# baseband.net
KiCad netlist of a schematic drawn in Altium Designer
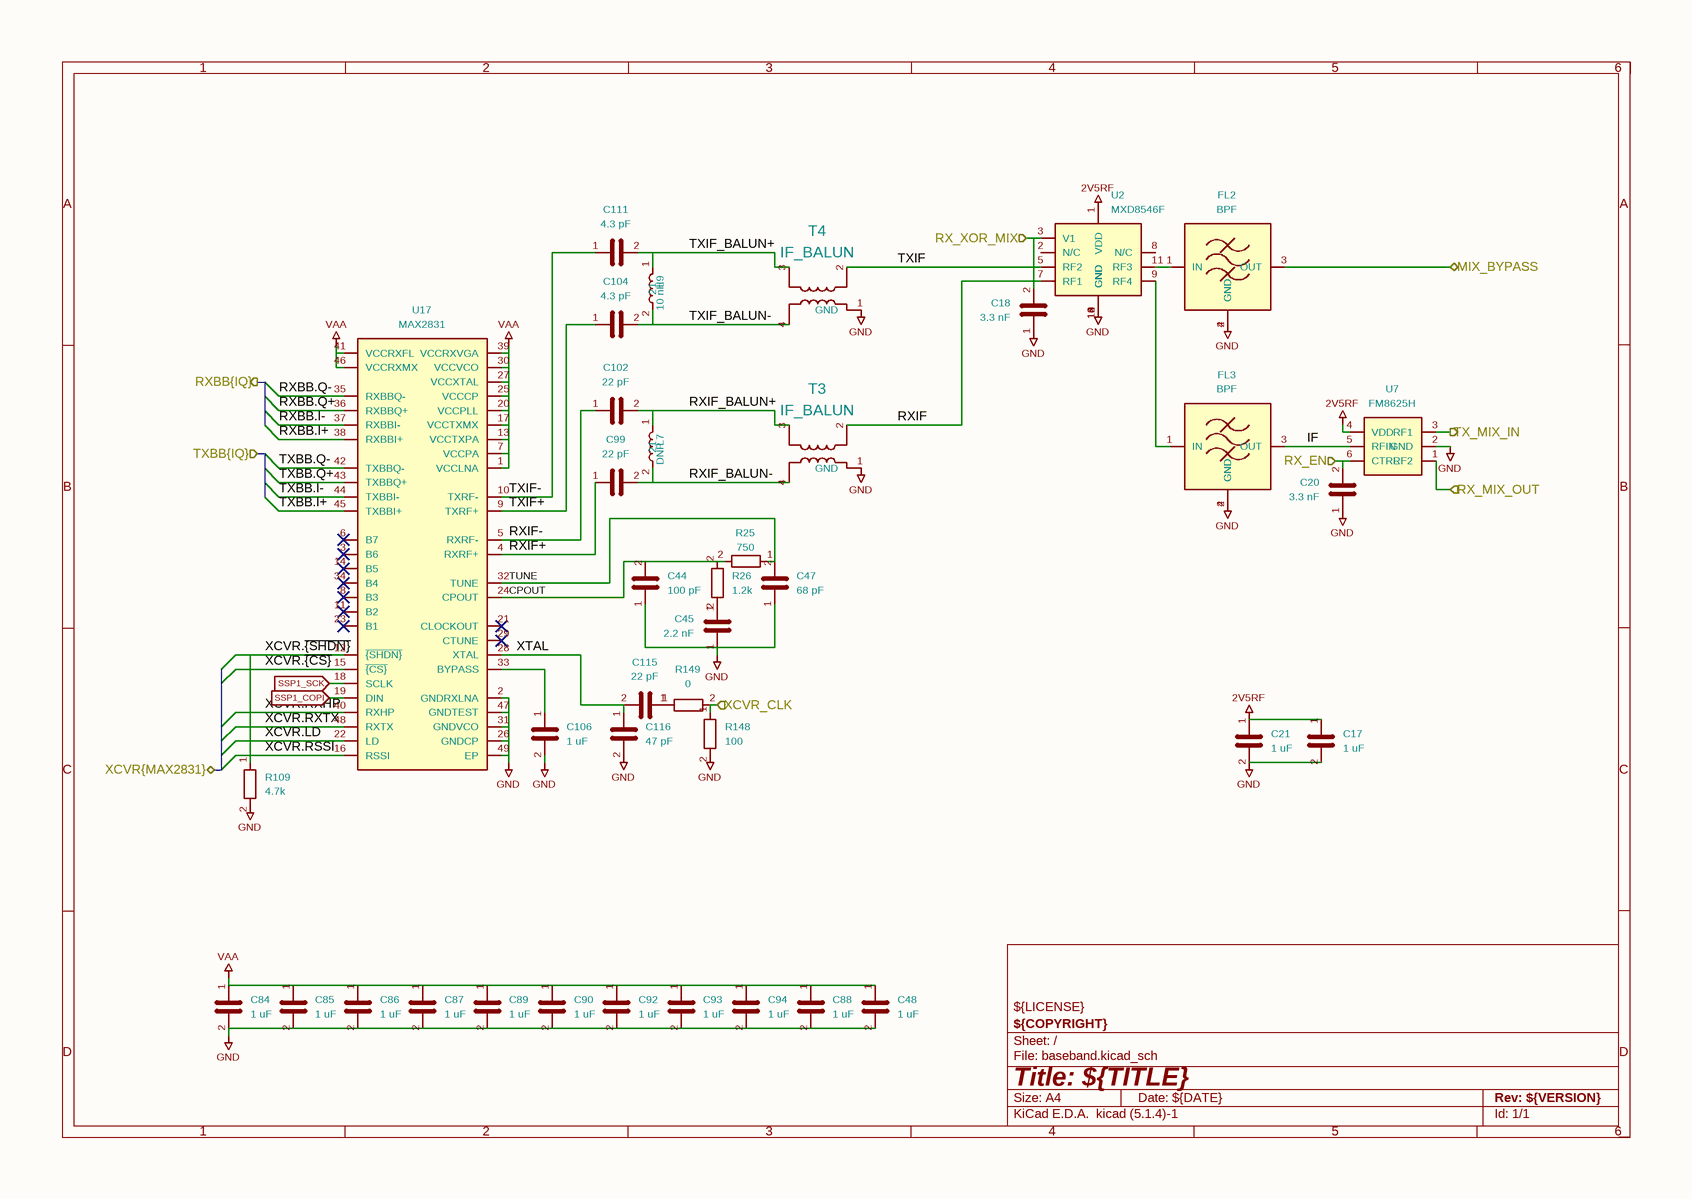
[diagram p0: baseband.SchDoc]

(export (version "E")
  (design (tool "Eeschema 10.0.6"))
  (components
    (comp (ref "C17")
      (value "1 uF")
      (footprint "C_0201_0603Metric")
      (description "CAP CER 1UF 10V X5R 0201")
      (fields (field (name "MANUFACTURER") "Murata") (field (name "PART NUMBER") "GRM033R61A105ME44D"))
      (libsource (lib "Device") (part "C"))
    )
    (comp (ref "C18")
      (value "3.3 nF")
      (footprint "C_0201_0603Metric")
      (description "CAP CER 3300PF 10V X7R 0201")
      (fields (field (name "MANUFACTURER") "Murata") (field (name "PART NUMBER") "GRM033R71A332KA01D"))
      (libsource (lib "Device") (part "C"))
    )
    (comp (ref "C20")
      (value "3.3 nF")
      (footprint "C_0201_0603Metric")
      (description "CAP CER 3300PF 10V X7R 0201")
      (fields (field (name "MANUFACTURER") "Murata") (field (name "PART NUMBER") "GRM033R71A332KA01D"))
      (libsource (lib "Device") (part "C"))
    )
    (comp (ref "C21")
      (value "1 uF")
      (footprint "C_0201_0603Metric")
      (description "CAP CER 1UF 10V X5R 0201")
      (fields (field (name "MANUFACTURER") "Murata") (field (name "PART NUMBER") "GRM033R61A105ME44D"))
      (libsource (lib "Device") (part "C"))
    )
    (comp (ref "C44")
      (value "100 pF")
      (footprint "C_0201_0603Metric")
      (description "CAP CER 100PF 25V C0G/NP0 0201")
      (fields (field (name "MANUFACTURER") "Murata") (field (name "PART NUMBER") "GRM0335C1E101JA01D"))
      (libsource (lib "Device") (part "C"))
    )
    (comp (ref "C45")
      (value "2.2 nF")
      (footprint "C_0201_0603Metric")
      (description "CAP CER 2200PF 10V X7R 0201")
      (fields (field (name "MANUFACTURER") "Murata") (field (name "PART NUMBER") "GRM033R71A222KA01D"))
      (libsource (lib "Device") (part "C"))
    )
    (comp (ref "C47")
      (value "68 pF")
      (footprint "C_0201_0603Metric")
      (description "CAP CER 68PF 50V C0G/NP0 0201")
      (fields (field (name "MANUFACTURER") "Murata") (field (name "PART NUMBER") "GRM0335C1H680JA01D"))
      (libsource (lib "Device") (part "C"))
    )
    (comp (ref "C48")
      (value "1 uF")
      (footprint "C_0201_0603Metric")
      (description "CAP CER 1UF 10V X5R 0201")
      (fields (field (name "MANUFACTURER") "Murata") (field (name "PART NUMBER") "GRM033R61A105ME44D"))
      (libsource (lib "Device") (part "C"))
    )
    (comp (ref "C84")
      (value "1 uF")
      (footprint "C_0201_0603Metric")
      (description "CAP CER 1UF 10V X5R 0201")
      (fields (field (name "MANUFACTURER") "Murata") (field (name "PART NUMBER") "GRM033R61A105ME44D"))
      (libsource (lib "Device") (part "C"))
    )
    (comp (ref "C85")
      (value "1 uF")
      (footprint "C_0201_0603Metric")
      (description "CAP CER 1UF 10V X5R 0201")
      (fields (field (name "MANUFACTURER") "Murata") (field (name "PART NUMBER") "GRM033R61A105ME44D"))
      (libsource (lib "Device") (part "C"))
    )
    (comp (ref "C86")
      (value "1 uF")
      (footprint "C_0201_0603Metric")
      (description "CAP CER 1UF 10V X5R 0201")
      (fields (field (name "MANUFACTURER") "Murata") (field (name "PART NUMBER") "GRM033R61A105ME44D"))
      (libsource (lib "Device") (part "C"))
    )
    (comp (ref "C87")
      (value "1 uF")
      (footprint "C_0201_0603Metric")
      (description "CAP CER 1UF 10V X5R 0201")
      (fields (field (name "MANUFACTURER") "Murata") (field (name "PART NUMBER") "GRM033R61A105ME44D"))
      (libsource (lib "Device") (part "C"))
    )
    (comp (ref "C88")
      (value "1 uF")
      (footprint "C_0201_0603Metric")
      (description "CAP CER 1UF 10V X5R 0201")
      (fields (field (name "MANUFACTURER") "Murata") (field (name "PART NUMBER") "GRM033R61A105ME44D"))
      (libsource (lib "Device") (part "C"))
    )
    (comp (ref "C89")
      (value "1 uF")
      (footprint "C_0201_0603Metric")
      (description "CAP CER 1UF 10V X5R 0201")
      (fields (field (name "MANUFACTURER") "Murata") (field (name "PART NUMBER") "GRM033R61A105ME44D"))
      (libsource (lib "Device") (part "C"))
    )
    (comp (ref "C90")
      (value "1 uF")
      (footprint "C_0201_0603Metric")
      (description "CAP CER 1UF 10V X5R 0201")
      (fields (field (name "MANUFACTURER") "Murata") (field (name "PART NUMBER") "GRM033R61A105ME44D"))
      (libsource (lib "Device") (part "C"))
    )
    (comp (ref "C92")
      (value "1 uF")
      (footprint "C_0201_0603Metric")
      (description "CAP CER 1UF 10V X5R 0201")
      (fields (field (name "MANUFACTURER") "Murata") (field (name "PART NUMBER") "GRM033R61A105ME44D"))
      (libsource (lib "Device") (part "C"))
    )
    (comp (ref "C93")
      (value "1 uF")
      (footprint "C_0201_0603Metric")
      (description "CAP CER 1UF 10V X5R 0201")
      (fields (field (name "MANUFACTURER") "Murata") (field (name "PART NUMBER") "GRM033R61A105ME44D"))
      (libsource (lib "Device") (part "C"))
    )
    (comp (ref "C94")
      (value "1 uF")
      (footprint "C_0201_0603Metric")
      (description "CAP CER 1UF 10V X5R 0201")
      (fields (field (name "MANUFACTURER") "Murata") (field (name "PART NUMBER") "GRM033R61A105ME44D"))
      (libsource (lib "Device") (part "C"))
    )
    (comp (ref "C99")
      (value "22 pF")
      (footprint "C_0201_0603Metric")
      (description "CAP CER 22PF 50V C0G/NP0 0201")
      (fields (field (name "MANUFACTURER") "Murata") (field (name "PART NUMBER") "GRM0335C1H220JA01D"))
      (libsource (lib "Device") (part "C"))
    )
    (comp (ref "C102")
      (value "22 pF")
      (footprint "C_0201_0603Metric")
      (description "CAP CER 22PF 50V C0G/NP0 0201")
      (fields (field (name "MANUFACTURER") "Murata") (field (name "PART NUMBER") "GRM0335C1H220JA01D"))
      (libsource (lib "Device") (part "C"))
    )
    (comp (ref "C104")
      (value "4.3 pF")
      (footprint "C_0201_0603Metric")
      (description "CAP CER 4.3PF 25V C0G/NP0 0201")
      (fields (field (name "MANUFACTURER") "Murata") (field (name "PART NUMBER") "GRM0335C1E4R3CA01D"))
      (libsource (lib "Device") (part "C"))
    )
    (comp (ref "C106")
      (value "1 uF")
      (footprint "C_0201_0603Metric")
      (description "CAP CER 1UF 10V X5R 0201")
      (fields (field (name "MANUFACTURER") "Murata") (field (name "PART NUMBER") "GRM033R61A105ME44D"))
      (libsource (lib "Device") (part "C"))
    )
    (comp (ref "C111")
      (value "4.3 pF")
      (footprint "C_0201_0603Metric")
      (description "CAP CER 4.3PF 25V C0G/NP0 0201")
      (fields (field (name "MANUFACTURER") "Murata") (field (name "PART NUMBER") "GRM0335C1E4R3CA01D"))
      (libsource (lib "Device") (part "C"))
    )
    (comp (ref "C115")
      (value "22 pF")
      (footprint "C_0201_0603Metric")
      (description "CAP CER 22PF 50V C0G/NP0 0201")
      (fields (field (name "MANUFACTURER") "Murata") (field (name "PART NUMBER") "GRM0335C1H220JA01D"))
      (libsource (lib "Device") (part "C"))
    )
    (comp (ref "C116")
      (value "47 pF")
      (footprint "C_0201_0603Metric")
      (description "CAP CER 47PF 25V C0G/NP0 0201")
      (fields (field (name "MANUFACTURER") "Murata") (field (name "PART NUMBER") "GRM0335C1E470JA01D"))
      (libsource (lib "Device") (part "C"))
    )
    (comp (ref "FL2")
      (value "BPF")
      (footprint "Filter_Pulse_BPF1608LM09R5000A")
      (description "RF FILTER BAND PASS 2.45GHZ 0603")
      (fields
        (field (name "MANUFACTURER") "Pulse Electronics")
        (field (name "PART NUMBER") "BPF1608LM02R2400A")
      )
      (libsource (lib "RF_Filter") (part "BFCN-1445"))
    )
    (comp (ref "FL3")
      (value "BPF")
      (footprint "Filter_Pulse_BPF1608LM09R5000A")
      (description "RF FILTER BAND PASS 2.45GHZ 0603")
      (fields
        (field (name "MANUFACTURER") "Pulse Electronics")
        (field (name "PART NUMBER") "BPF1608LM02R2400A")
      )
      (libsource (lib "RF_Filter") (part "BFCN-1445"))
    )
    (comp (ref "L7") (value "DNP") (footprint "L_0201_0603Metric") (libsource (lib "Device") (part "L")))
    (comp (ref "L9")
      (value "10 nH")
      (footprint "L_0201_0603Metric")
      (description "FIXED IND 10NH 250MA 700MOHM SMD")
      (fields (field (name "MANUFACTURER") "Murata") (field (name "PART NUMBER") "LQP03TN10NJ02D"))
      (libsource (lib "Device") (part "L"))
    )
    (comp (ref "R25")
      (value "750")
      (footprint "R_0201_0603Metric")
      (description "RES 750 OHM 5% 1/20W 0201")
      (fields (field (name "MANUFACTURER") "Yageo") (field (name "PART NUMBER") "RC0201JR-07750RL"))
      (libsource (lib "") (part "R_1"))
    )
    (comp (ref "R26")
      (value "1.2k")
      (footprint "R_0201_0603Metric")
      (description "RES 1.2K OHM 5% 1/20W 0201")
      (fields (field (name "MANUFACTURER") "Yageo") (field (name "PART NUMBER") "RC0201JR-071K2L"))
      (libsource (lib "Device") (part "R"))
    )
    (comp (ref "R109")
      (value "4.7k")
      (footprint "R_0201_0603Metric")
      (description "RES 4.7K OHM 1% 1/20W 0201")
      (fields (field (name "MANUFACTURER") "Yageo") (field (name "PART NUMBER") "RC0201FR-074K7L"))
      (libsource (lib "") (part "R_1"))
    )
    (comp (ref "R148")
      (value "100")
      (footprint "R_0201_0603Metric")
      (description "RES 100 OHM 5% 1/20W 0201")
      (fields (field (name "MANUFACTURER") "Yageo") (field (name "PART NUMBER") "RC0201JR-07100RL"))
      (libsource (lib "") (part "R_1"))
    )
    (comp (ref "R149")
      (value "0")
      (footprint "R_0201_0603Metric")
      (description "RES 0 OHM JUMPER 1/20W 0201")
      (fields (field (name "MANUFACTURER") "Yageo") (field (name "PART NUMBER") "RC0201JR-070RL"))
      (libsource (lib "Device") (part "R"))
    )
    (comp (ref "T3")
      (value "IF_BALUN")
      (footprint "Balun_TDK_TFSZ06052460-3310A2X")
      (description "Thin-Film Balun for 2300-2690MHz")
      (fields (field (name "MANUFACTURER") "TDK") (field (name "PART NUMBER") "TFSZ06052460-3310A2X"))
      (libsource (lib "praline") (part "TFSZ06052460-3310A2X"))
    )
    (comp (ref "T4")
      (value "IF_BALUN")
      (footprint "Balun_TDK_TFSZ06052460-3310A2X")
      (description "Thin-Film Balun for 2300-2690MHz")
      (fields (field (name "MANUFACTURER") "TDK") (field (name "PART NUMBER") "TFSZ06052460-3310A2X"))
      (libsource (lib "praline") (part "TFSZ06052460-3310A2X"))
    )
    (comp (ref "U2")
      (value "MXD8546F")
      (footprint "QFN-12-1EP_2x2mm_P0.5mm_EP1x1mm")
      (description "X-DPDT RF SWITCH")
      (fields (field (name "MANUFACTURER") "Maxscend"))
      (libsource (lib "praline") (part "MXD8546F"))
    )
    (comp (ref "U7")
      (value "FM8625H")
      (footprint "TSLP-6-4_1.1x0.7mm_P0.4mm")
      (description "SPDT RF SWITCH")
      (fields (field (name "MANUFACTURER") "Shenzhen Fuman"))
      (libsource (lib "praline") (part "BGS12P2L6"))
    )
    (comp (ref "U17")
      (value "MAX2831")
      (footprint "QFN-48-1EP_7x7mm_P0.5mm_EP5.6x5.6mm_ThermalVias")
      (description "IC RF TXRX WIFI 48TQFN")
      (fields (field (name "MANUFACTURER") "Maxim") (field (name "PART NUMBER") "MAX2831ETM+T"))
      (libsource (lib "praline") (part "MAX2831"))
    )
  )
  (nets
    (net (code "4") (name "/CPOUT") (class "Default")
      (node (ref "C44") (pin "2") (pinfunction "2_2") (pintype "passive"))
      (node (ref "R25") (pin "2") (pinfunction "2_2") (pintype "passive"))
      (node (ref "R26") (pin "2") (pinfunction "2_2") (pintype "passive"))
      (node (ref "U17") (pin "24") (pinfunction "CPOUT_24") (pintype "passive"))
    )
    (net (code "5") (name "/IF") (class "Default")
      (node (ref "FL3") (pin "3") (pinfunction "OUT_3") (pintype "passive"))
      (node (ref "U7") (pin "5") (pinfunction "RFIN_5") (pintype "passive"))
    )
    (net (code "6") (name "/MIX_BYPASS") (class "Default")
      (node (ref "FL2") (pin "3") (pinfunction "OUT_3") (pintype "passive"))
    )
    (net (code "7") (name "/RXBB.I+") (class "Default")
      (node (ref "U17") (pin "38") (pinfunction "RXBBI+_38") (pintype "passive"))
    )
    (net (code "8") (name "/RXBB.I-") (class "Default")
      (node (ref "U17") (pin "37") (pinfunction "RXBBI-_37") (pintype "passive"))
    )
    (net (code "9") (name "/RXBB.Q+") (class "Default")
      (node (ref "U17") (pin "36") (pinfunction "RXBBQ+_36") (pintype "passive"))
    )
    (net (code "10") (name "/RXBB.Q-") (class "Default")
      (node (ref "U17") (pin "35") (pinfunction "RXBBQ-_35") (pintype "passive"))
    )
    (net (code "12") (name "/RXIF") (class "Default")
      (node (ref "T3") (pin "2") (pinfunction "2_2") (pintype "passive"))
      (node (ref "U2") (pin "7") (pinfunction "RF1_7") (pintype "passive"))
    )
    (net (code "13") (name "/RXIF+") (class "Default")
      (node (ref "C99") (pin "1") (pinfunction "1_1") (pintype "passive"))
      (node (ref "U17") (pin "4") (pinfunction "RXRF+_4") (pintype "passive"))
    )
    (net (code "14") (name "/RXIF-") (class "Default")
      (node (ref "C102") (pin "1") (pinfunction "1_1") (pintype "passive"))
      (node (ref "U17") (pin "5") (pinfunction "RXRF-_5") (pintype "passive"))
    )
    (net (code "15") (name "/RXIF_BALUN+") (class "Default")
      (node (ref "C102") (pin "2") (pinfunction "2_2") (pintype "passive"))
      (node (ref "L7") (pin "1") (pinfunction "1_1") (pintype "passive"))
      (node (ref "T3") (pin "3") (pinfunction "3_3") (pintype "passive"))
    )
    (net (code "16") (name "/RXIF_BALUN-") (class "Default")
      (node (ref "C99") (pin "2") (pinfunction "2_2") (pintype "passive"))
      (node (ref "L7") (pin "2") (pinfunction "2_2") (pintype "passive"))
      (node (ref "T3") (pin "4") (pinfunction "4_4") (pintype "passive"))
    )
    (net (code "17") (name "/RX_EN") (class "Default")
      (node (ref "C20") (pin "2") (pinfunction "2_2") (pintype "passive"))
      (node (ref "U7") (pin "6") (pinfunction "CTRL_6") (pintype "passive"))
    )
    (net (code "18") (name "/RX_MIX_OUT") (class "Default")
      (node (ref "U7") (pin "1") (pinfunction "RF2_1") (pintype "passive"))
    )
    (net (code "19") (name "/RX_XOR_MIX") (class "Default")
      (node (ref "C18") (pin "2") (pinfunction "2_2") (pintype "passive"))
      (node (ref "U2") (pin "3") (pinfunction "V1_3") (pintype "passive"))
    )
    (net (code "20") (name "/SSP1_COPI") (class "Default")
      (node (ref "U17") (pin "19") (pinfunction "DIN_19") (pintype "passive"))
    )
    (net (code "21") (name "/SSP1_SCK") (class "Default")
      (node (ref "U17") (pin "18") (pinfunction "SCLK_18") (pintype "passive"))
    )
    (net (code "22") (name "/TUNE") (class "Default")
      (node (ref "C47") (pin "2") (pinfunction "2_2") (pintype "passive"))
      (node (ref "R25") (pin "1") (pinfunction "1_1") (pintype "passive"))
      (node (ref "U17") (pin "32") (pinfunction "TUNE_32") (pintype "passive"))
    )
    (net (code "23") (name "/TXBB.I+") (class "Default")
      (node (ref "U17") (pin "45") (pinfunction "TXBBI+_45") (pintype "passive"))
    )
    (net (code "24") (name "/TXBB.I-") (class "Default")
      (node (ref "U17") (pin "44") (pinfunction "TXBBI-_44") (pintype "passive"))
    )
    (net (code "25") (name "/TXBB.Q+") (class "Default")
      (node (ref "U17") (pin "43") (pinfunction "TXBBQ+_43") (pintype "passive"))
    )
    (net (code "26") (name "/TXBB.Q-") (class "Default")
      (node (ref "U17") (pin "42") (pinfunction "TXBBQ-_42") (pintype "passive"))
    )
    (net (code "28") (name "/TXIF") (class "Default")
      (node (ref "T4") (pin "2") (pinfunction "2_2") (pintype "passive"))
      (node (ref "U2") (pin "5") (pinfunction "RF2_5") (pintype "passive"))
    )
    (net (code "29") (name "/TXIF+") (class "Default")
      (node (ref "C104") (pin "1") (pinfunction "1_1") (pintype "passive"))
      (node (ref "U17") (pin "9") (pinfunction "TXRF+_9") (pintype "passive"))
    )
    (net (code "30") (name "/TXIF-") (class "Default")
      (node (ref "C111") (pin "1") (pinfunction "1_1") (pintype "passive"))
      (node (ref "U17") (pin "10") (pinfunction "TXRF-_10") (pintype "passive"))
    )
    (net (code "31") (name "/TXIF_BALUN+") (class "Default")
      (node (ref "C111") (pin "2") (pinfunction "2_2") (pintype "passive"))
      (node (ref "L9") (pin "1") (pinfunction "1_1") (pintype "passive"))
      (node (ref "T4") (pin "3") (pinfunction "3_3") (pintype "passive"))
    )
    (net (code "32") (name "/TXIF_BALUN-") (class "Default")
      (node (ref "C104") (pin "2") (pinfunction "2_2") (pintype "passive"))
      (node (ref "L9") (pin "2") (pinfunction "2_2") (pintype "passive"))
      (node (ref "T4") (pin "4") (pinfunction "4_4") (pintype "passive"))
    )
    (net (code "33") (name "/TX_MIX_IN") (class "Default")
      (node (ref "U7") (pin "3") (pinfunction "RF1_3") (pintype "passive"))
    )
    (net (code "34") (name "/XCVR.LD") (class "Default")
      (node (ref "U17") (pin "22") (pinfunction "LD_22") (pintype "passive"))
    )
    (net (code "35") (name "/XCVR.RSSI") (class "Default")
      (node (ref "U17") (pin "16") (pinfunction "RSSI_16") (pintype "passive"))
    )
    (net (code "36") (name "/XCVR.RXHP") (class "Default")
      (node (ref "U17") (pin "40") (pinfunction "RXHP_40") (pintype "passive"))
    )
    (net (code "37") (name "/XCVR.RXTX") (class "Default")
      (node (ref "U17") (pin "48") (pinfunction "RXTX_48") (pintype "passive"))
    )
    (net (code "38") (name "/XCVR.~{{CS}}") (class "Default")
      (node (ref "U17") (pin "15") (pinfunction "~{{CS}}_15") (pintype "passive"))
    )
    (net (code "39") (name "/XCVR.~{{SHDN}}") (class "Default")
      (node (ref "R109") (pin "1") (pinfunction "1_1") (pintype "passive"))
      (node (ref "U17") (pin "12") (pinfunction "~{{SHDN}}_12") (pintype "passive"))
    )
    (net (code "40") (name "/XCVR_CLK") (class "Default")
      (node (ref "R148") (pin "1") (pinfunction "1_1") (pintype "passive"))
      (node (ref "R149") (pin "2") (pinfunction "2_2") (pintype "passive"))
    )
    (net (code "42") (name "/XTAL") (class "Default")
      (node (ref "C115") (pin "2") (pinfunction "2_2") (pintype "passive"))
      (node (ref "C116") (pin "1") (pinfunction "1_1") (pintype "passive"))
      (node (ref "U17") (pin "28") (pinfunction "XTAL_28") (pintype "passive"))
    )
    (net (code "43") (name "2V5RF") (class "Default")
      (node (ref "C17") (pin "1") (pinfunction "1_1") (pintype "passive"))
      (node (ref "C21") (pin "1") (pinfunction "1_1") (pintype "passive"))
      (node (ref "U2") (pin "1") (pinfunction "VDD_1") (pintype "passive"))
      (node (ref "U7") (pin "4") (pinfunction "VDD_4") (pintype "passive"))
    )
    (net (code "44") (name "GND") (class "Default")
      (node (ref "C106") (pin "2") (pinfunction "2_2") (pintype "passive"))
      (node (ref "C116") (pin "2") (pinfunction "2_2") (pintype "passive"))
      (node (ref "C17") (pin "2") (pinfunction "2_2") (pintype "passive"))
      (node (ref "C18") (pin "1") (pinfunction "1_1") (pintype "passive"))
      (node (ref "C20") (pin "1") (pinfunction "1_1") (pintype "passive"))
      (node (ref "C21") (pin "2") (pinfunction "2_2") (pintype "passive"))
      (node (ref "C44") (pin "1") (pinfunction "1_1") (pintype "passive"))
      (node (ref "C45") (pin "1") (pinfunction "1_1") (pintype "passive"))
      (node (ref "C47") (pin "1") (pinfunction "1_1") (pintype "passive"))
      (node (ref "C48") (pin "2") (pinfunction "2_2") (pintype "passive"))
      (node (ref "C84") (pin "2") (pinfunction "2_2") (pintype "passive"))
      (node (ref "C85") (pin "2") (pinfunction "2_2") (pintype "passive"))
      (node (ref "C86") (pin "2") (pinfunction "2_2") (pintype "passive"))
      (node (ref "C87") (pin "2") (pinfunction "2_2") (pintype "passive"))
      (node (ref "C88") (pin "2") (pinfunction "2_2") (pintype "passive"))
      (node (ref "C89") (pin "2") (pinfunction "2_2") (pintype "passive"))
      (node (ref "C90") (pin "2") (pinfunction "2_2") (pintype "passive"))
      (node (ref "C92") (pin "2") (pinfunction "2_2") (pintype "passive"))
      (node (ref "C93") (pin "2") (pinfunction "2_2") (pintype "passive"))
      (node (ref "C94") (pin "2") (pinfunction "2_2") (pintype "passive"))
      (node (ref "FL2") (pin "2") (pinfunction "GND_2") (pintype "passive"))
      (node (ref "FL2") (pin "4") (pinfunction "GND_4") (pintype "passive"))
      (node (ref "FL3") (pin "2") (pinfunction "GND_2") (pintype "passive"))
      (node (ref "FL3") (pin "4") (pinfunction "GND_4") (pintype "passive"))
      (node (ref "R109") (pin "2") (pinfunction "2_2") (pintype "passive"))
      (node (ref "R148") (pin "2") (pinfunction "2_2") (pintype "passive"))
      (node (ref "T3") (pin "1") (pinfunction "GND_1") (pintype "passive"))
      (node (ref "T4") (pin "1") (pinfunction "GND_1") (pintype "passive"))
      (node (ref "U17") (pin "2") (pinfunction "GNDRXLNA_2") (pintype "passive"))
      (node (ref "U17") (pin "26") (pinfunction "GNDCP_26") (pintype "passive"))
      (node (ref "U17") (pin "31") (pinfunction "GNDVCO_31") (pintype "passive"))
      (node (ref "U17") (pin "47") (pinfunction "GNDTEST_47") (pintype "passive"))
      (node (ref "U17") (pin "49") (pinfunction "EP_49") (pintype "passive"))
      (node (ref "U2") (pin "10") (pinfunction "GND_10") (pintype "passive"))
      (node (ref "U2") (pin "12") (pinfunction "GND_12") (pintype "passive"))
      (node (ref "U2") (pin "13") (pinfunction "GND_13") (pintype "passive"))
      (node (ref "U2") (pin "4") (pinfunction "GND_4") (pintype "passive"))
      (node (ref "U2") (pin "6") (pinfunction "GND_6") (pintype "passive"))
      (node (ref "U7") (pin "2") (pinfunction "GND_2") (pintype "passive"))
    )
    (net (code "45") (name "Net-(C45-Pad2)") (class "Default")
      (node (ref "C45") (pin "2") (pinfunction "2_2") (pintype "passive"))
      (node (ref "R26") (pin "1") (pinfunction "1_1") (pintype "passive"))
    )
    (net (code "46") (name "Net-(C115-Pad1)") (class "Default")
      (node (ref "C115") (pin "1") (pinfunction "1_1") (pintype "passive"))
      (node (ref "R149") (pin "1") (pinfunction "1_1") (pintype "passive"))
    )
    (net (code "47") (name "Net-(FL2-IN)") (class "Default")
      (node (ref "FL2") (pin "1") (pinfunction "IN_1") (pintype "passive"))
      (node (ref "U2") (pin "11") (pinfunction "RF3_11") (pintype "passive"))
    )
    (net (code "48") (name "Net-(FL3-IN)") (class "Default")
      (node (ref "FL3") (pin "1") (pinfunction "IN_1") (pintype "passive"))
      (node (ref "U2") (pin "9") (pinfunction "RF4_9") (pintype "passive"))
    )
    (net (code "49") (name "Net-(U17-BYPASS)") (class "Default")
      (node (ref "C106") (pin "1") (pinfunction "1_1") (pintype "passive"))
      (node (ref "U17") (pin "33") (pinfunction "BYPASS_33") (pintype "passive"))
    )
    (net (code "50") (name "VAA") (class "Default")
      (node (ref "C48") (pin "1") (pinfunction "1_1") (pintype "passive"))
      (node (ref "C84") (pin "1") (pinfunction "1_1") (pintype "passive"))
      (node (ref "C85") (pin "1") (pinfunction "1_1") (pintype "passive"))
      (node (ref "C86") (pin "1") (pinfunction "1_1") (pintype "passive"))
      (node (ref "C87") (pin "1") (pinfunction "1_1") (pintype "passive"))
      (node (ref "C88") (pin "1") (pinfunction "1_1") (pintype "passive"))
      (node (ref "C89") (pin "1") (pinfunction "1_1") (pintype "passive"))
      (node (ref "C90") (pin "1") (pinfunction "1_1") (pintype "passive"))
      (node (ref "C92") (pin "1") (pinfunction "1_1") (pintype "passive"))
      (node (ref "C93") (pin "1") (pinfunction "1_1") (pintype "passive"))
      (node (ref "C94") (pin "1") (pinfunction "1_1") (pintype "passive"))
      (node (ref "U17") (pin "1") (pinfunction "VCCLNA_1") (pintype "passive"))
      (node (ref "U17") (pin "13") (pinfunction "VCCTXPA_13") (pintype "passive"))
      (node (ref "U17") (pin "17") (pinfunction "VCCTXMX_17") (pintype "passive"))
      (node (ref "U17") (pin "20") (pinfunction "VCCPLL_20") (pintype "passive"))
      (node (ref "U17") (pin "25") (pinfunction "VCCCP_25") (pintype "passive"))
      (node (ref "U17") (pin "27") (pinfunction "VCCXTAL_27") (pintype "passive"))
      (node (ref "U17") (pin "30") (pinfunction "VCCVCO_30") (pintype "passive"))
      (node (ref "U17") (pin "39") (pinfunction "VCCRXVGA_39") (pintype "passive"))
      (node (ref "U17") (pin "41") (pinfunction "VCCRXFL_41") (pintype "passive"))
      (node (ref "U17") (pin "46") (pinfunction "VCCRXMX_46") (pintype "passive"))
      (node (ref "U17") (pin "7") (pinfunction "VCCPA_7") (pintype "passive"))
    )
    (net (code "51") (name "unconnected-(U2-N{slash}C-Pad2)") (class "Default")
      (node (ref "U2") (pin "2") (pinfunction "N/C_2") (pintype "passive"))
    )
    (net (code "52") (name "unconnected-(U2-N{slash}C-Pad8)") (class "Default")
      (node (ref "U2") (pin "8") (pinfunction "N/C_8") (pintype "passive"))
    )
    (net (code "53") (name "unconnected-(U17-B1-Pad23)") (class "Default")
      (node (ref "U17") (pin "23") (pinfunction "B1_23") (pintype "passive+no_connect"))
    )
    (net (code "54") (name "unconnected-(U17-B2-Pad11)") (class "Default")
      (node (ref "U17") (pin "11") (pinfunction "B2_11") (pintype "passive+no_connect"))
    )
    (net (code "55") (name "unconnected-(U17-B3-Pad8)") (class "Default")
      (node (ref "U17") (pin "8") (pinfunction "B3_8") (pintype "passive+no_connect"))
    )
    (net (code "56") (name "unconnected-(U17-B4-Pad34)") (class "Default")
      (node (ref "U17") (pin "34") (pinfunction "B4_34") (pintype "passive+no_connect"))
    )
    (net (code "57") (name "unconnected-(U17-B5-Pad14)") (class "Default")
      (node (ref "U17") (pin "14") (pinfunction "B5_14") (pintype "passive+no_connect"))
    )
    (net (code "58") (name "unconnected-(U17-B6-Pad3)") (class "Default")
      (node (ref "U17") (pin "3") (pinfunction "B6_3") (pintype "passive+no_connect"))
    )
    (net (code "59") (name "unconnected-(U17-B7-Pad6)") (class "Default")
      (node (ref "U17") (pin "6") (pinfunction "B7_6") (pintype "passive+no_connect"))
    )
    (net (code "60") (name "unconnected-(U17-CLOCKOUT-Pad21)") (class "Default")
      (node (ref "U17") (pin "21") (pinfunction "CLOCKOUT_21") (pintype "passive+no_connect"))
    )
    (net (code "61") (name "unconnected-(U17-CTUNE-Pad29)") (class "Default")
      (node (ref "U17") (pin "29") (pinfunction "CTUNE_29") (pintype "passive+no_connect"))
    )
  )
)
